# cSLIM-SA_FRAM.net
KiCad netlist of a schematic drawn in Altium Designer
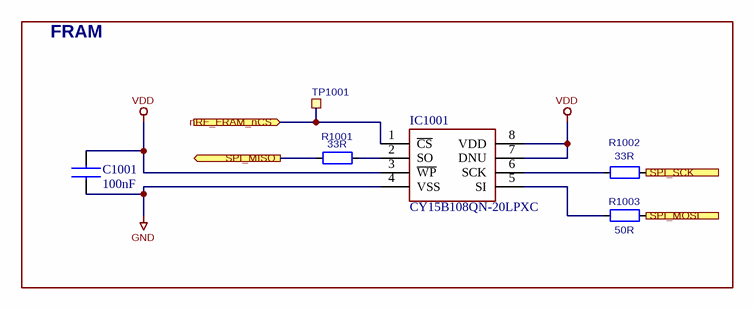
[diagram p0: cSLIM-SA_FRAM.SchDoc]

(export (version "E")
  (design (tool "Eeschema 10.0.6"))
  (components
    (comp (ref "C1001")
      (value "100nF")
      (footprint "cSLIM-SA:CAPC1608X90N")
      (description "Capacitor")
      (fields
        (field (name "MANUFACTURER_PART_NUMBER") "06033G104ZAT2A")
        (field (name "MOUSER PART NUMBER") "581-06033G104Z")
      )
      (libsource (lib "cSLIM-SA") (part "C"))
    )
    (comp (ref "IC1001")
      (value "CY15B108QN-20LPXC")
      (footprint "cSLIM-SA:SON65P323X328X55-8N")
      (description "Integrated Circuit")
      (fields (field (name "MOUSER PART NUMBER") "727-CY15B108QN20LPXC"))
      (libsource (lib "cSLIM-SA") (part "CY15B108QN-20LPXC"))
    )
    (comp (ref "R1001") (value "33R") (footprint "RESC1608X55N") (libsource (lib "") (part "R_1")))
    (comp (ref "R1002") (value "33R") (footprint "RESC1608X55N") (libsource (lib "cSLIM-SA") (part "R")))
    (comp (ref "R1003") (value "50R") (footprint "RESC1608X55N") (libsource (lib "cSLIM-SA") (part "R")))
    (comp (ref "TP1001")
      (value "~")
      (footprint "cSLIM-SA:TP_SMD_Ø1.0mm")
      (libsource (lib "cSLIM-SA") (part "TP"))
    )
  )
  (nets
    (net (code "1") (name "/SPI_MISO") (class "Default")
      (node (ref "R1001") (pin "1") (pinfunction "1_1") (pintype "passive"))
    )
    (net (code "2") (name "/SPI_MOSI") (class "Default")
      (node (ref "R1003") (pin "1") (pinfunction "1_1") (pintype "passive"))
    )
    (net (code "3") (name "/SPI_SCK") (class "Default")
      (node (ref "R1002") (pin "1") (pinfunction "1_1") (pintype "passive"))
    )
    (net (code "4") (name "/nRF_FRAM_nCS") (class "Default")
      (node (ref "IC1001") (pin "1") (pinfunction "~{CS}_1") (pintype "passive"))
      (node (ref "TP1001") (pin "1") (pinfunction "1_1") (pintype "passive"))
    )
    (net (code "5") (name "GND") (class "Default")
      (node (ref "C1001") (pin "2") (pinfunction "2_2") (pintype "passive"))
      (node (ref "IC1001") (pin "4") (pinfunction "VSS_4") (pintype "passive"))
    )
    (net (code "6") (name "Net-(IC1001-SCK)") (class "Default")
      (node (ref "IC1001") (pin "6") (pinfunction "SCK_6") (pintype "passive"))
      (node (ref "R1002") (pin "2") (pinfunction "2_2") (pintype "passive"))
    )
    (net (code "7") (name "Net-(IC1001-SI)") (class "Default")
      (node (ref "IC1001") (pin "5") (pinfunction "SI_5") (pintype "passive"))
      (node (ref "R1003") (pin "2") (pinfunction "2_2") (pintype "passive"))
    )
    (net (code "8") (name "Net-(IC1001-SO)") (class "Default")
      (node (ref "IC1001") (pin "2") (pinfunction "SO_2") (pintype "passive"))
      (node (ref "R1001") (pin "2") (pinfunction "2_2") (pintype "passive"))
    )
    (net (code "9") (name "VDD") (class "Default")
      (node (ref "C1001") (pin "1") (pinfunction "1_1") (pintype "passive"))
      (node (ref "IC1001") (pin "3") (pinfunction "~{WP}_3") (pintype "passive"))
      (node (ref "IC1001") (pin "7") (pinfunction "DNU_7") (pintype "passive"))
      (node (ref "IC1001") (pin "8") (pinfunction "VDD_8") (pintype "passive"))
    )
  )
)
